# Sh1.net
KiCad netlist of a schematic drawn in Altium Designer
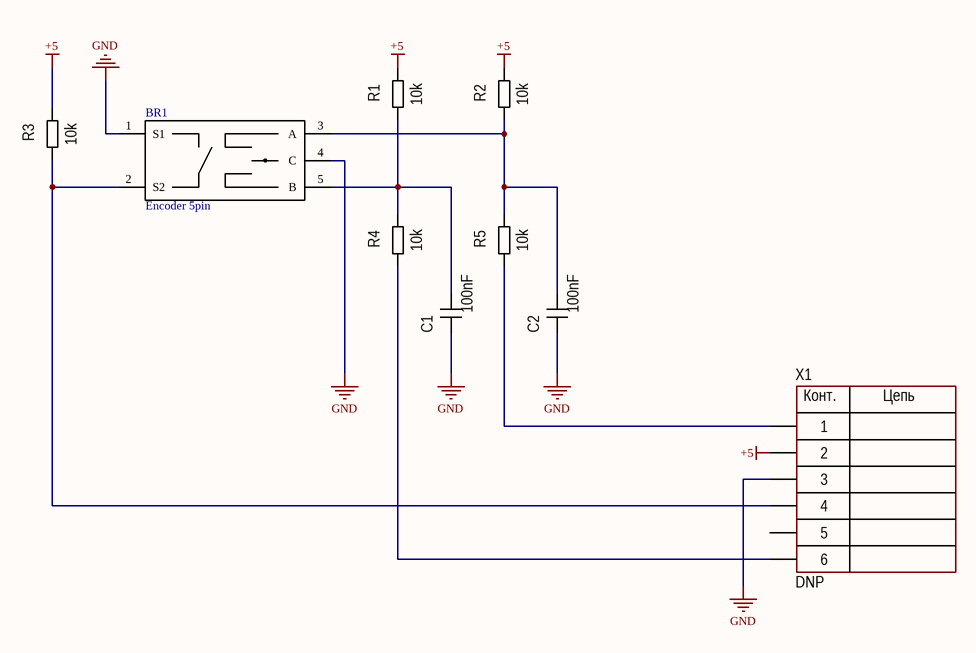
[diagram p0: Sh1.SchDoc]

(export (version "E")
  (design (tool "Eeschema 10.0.6"))
  (components
    (comp (ref "BR1")
      (value "Encoder 5pin")
      (footprint "Enc-5pin")
      (libsource (lib "Connectors") (part "Encoder 5pin"))
    )
    (comp (ref "C1")
      (value "100nF")
      (footprint "CH0603C")
      (libsource (lib "Condensators") (part "Capacitor"))
    )
    (comp (ref "C2")
      (value "100nF")
      (footprint "CH0603C")
      (libsource (lib "Condensators") (part "Capacitor"))
    )
    (comp (ref "R1")
      (value "10k")
      (footprint "standard:CH0603R")
      (libsource (lib "Resistors") (part "Resistor"))
    )
    (comp (ref "R2")
      (value "10k")
      (footprint "standard:CH0603R")
      (libsource (lib "Resistors") (part "Resistor"))
    )
    (comp (ref "R3")
      (value "10k")
      (footprint "standard:CH0603R")
      (libsource (lib "Resistors") (part "Resistor"))
    )
    (comp (ref "R4")
      (value "10k")
      (footprint "standard:CH0603R")
      (libsource (lib "Resistors") (part "Resistor"))
    )
    (comp (ref "R5")
      (value "10k")
      (footprint "standard:CH0603R")
      (libsource (lib "Resistors") (part "Resistor"))
    )
    (comp (ref "X1")
      (value "DNP")
      (footprint "CON: PBD-6")
      (libsource (lib "Connectors") (part "6-Connector"))
    )
  )
  (nets
    (net (code "1") (name "+5") (class "Default")
      (node (ref "R1") (pin "2") (pinfunction "2_2") (pintype "passive"))
      (node (ref "R2") (pin "2") (pinfunction "2_2") (pintype "passive"))
      (node (ref "R3") (pin "2") (pinfunction "2_2") (pintype "passive"))
      (node (ref "X1") (pin "2") (pinfunction "2_2") (pintype "passive"))
    )
    (net (code "2") (name "GND") (class "Default")
      (node (ref "BR1") (pin "1") (pinfunction "S1_1") (pintype "passive"))
      (node (ref "BR1") (pin "4") (pinfunction "C_4") (pintype "passive"))
      (node (ref "C1") (pin "1") (pinfunction "1_1") (pintype "passive"))
      (node (ref "C2") (pin "1") (pinfunction "1_1") (pintype "passive"))
      (node (ref "X1") (pin "3") (pinfunction "3_3") (pintype "power_in"))
    )
    (net (code "3") (name "Net-(BR1-A)") (class "Default")
      (node (ref "BR1") (pin "3") (pinfunction "A_3") (pintype "passive"))
      (node (ref "C2") (pin "2") (pinfunction "2_2") (pintype "passive"))
      (node (ref "R2") (pin "1") (pinfunction "1_1") (pintype "passive"))
      (node (ref "R5") (pin "2") (pinfunction "2_2") (pintype "passive"))
    )
    (net (code "4") (name "Net-(BR1-B)") (class "Default")
      (node (ref "BR1") (pin "5") (pinfunction "B_5") (pintype "passive"))
      (node (ref "C1") (pin "2") (pinfunction "2_2") (pintype "passive"))
      (node (ref "R1") (pin "1") (pinfunction "1_1") (pintype "passive"))
      (node (ref "R4") (pin "2") (pinfunction "2_2") (pintype "passive"))
    )
    (net (code "5") (name "Net-(BR1-S2)") (class "Default")
      (node (ref "BR1") (pin "2") (pinfunction "S2_2") (pintype "passive"))
      (node (ref "R3") (pin "1") (pinfunction "1_1") (pintype "passive"))
      (node (ref "X1") (pin "4") (pinfunction "4_4") (pintype "power_in"))
    )
    (net (code "6") (name "Net-(R4-Pad1)") (class "Default")
      (node (ref "R4") (pin "1") (pinfunction "1_1") (pintype "passive"))
      (node (ref "X1") (pin "6") (pinfunction "6_6") (pintype "power_in"))
    )
    (net (code "7") (name "Net-(R5-Pad1)") (class "Default")
      (node (ref "R5") (pin "1") (pinfunction "1_1") (pintype "passive"))
      (node (ref "X1") (pin "1") (pinfunction "1_1") (pintype "passive"))
    )
    (net (code "8") (name "unconnected-(X1-Pad5)") (class "Default")
      (node (ref "X1") (pin "5") (pinfunction "5_5") (pintype "power_in"))
    )
  )
)
